# Interface.net
KiCad netlist of a schematic drawn in EAGLE
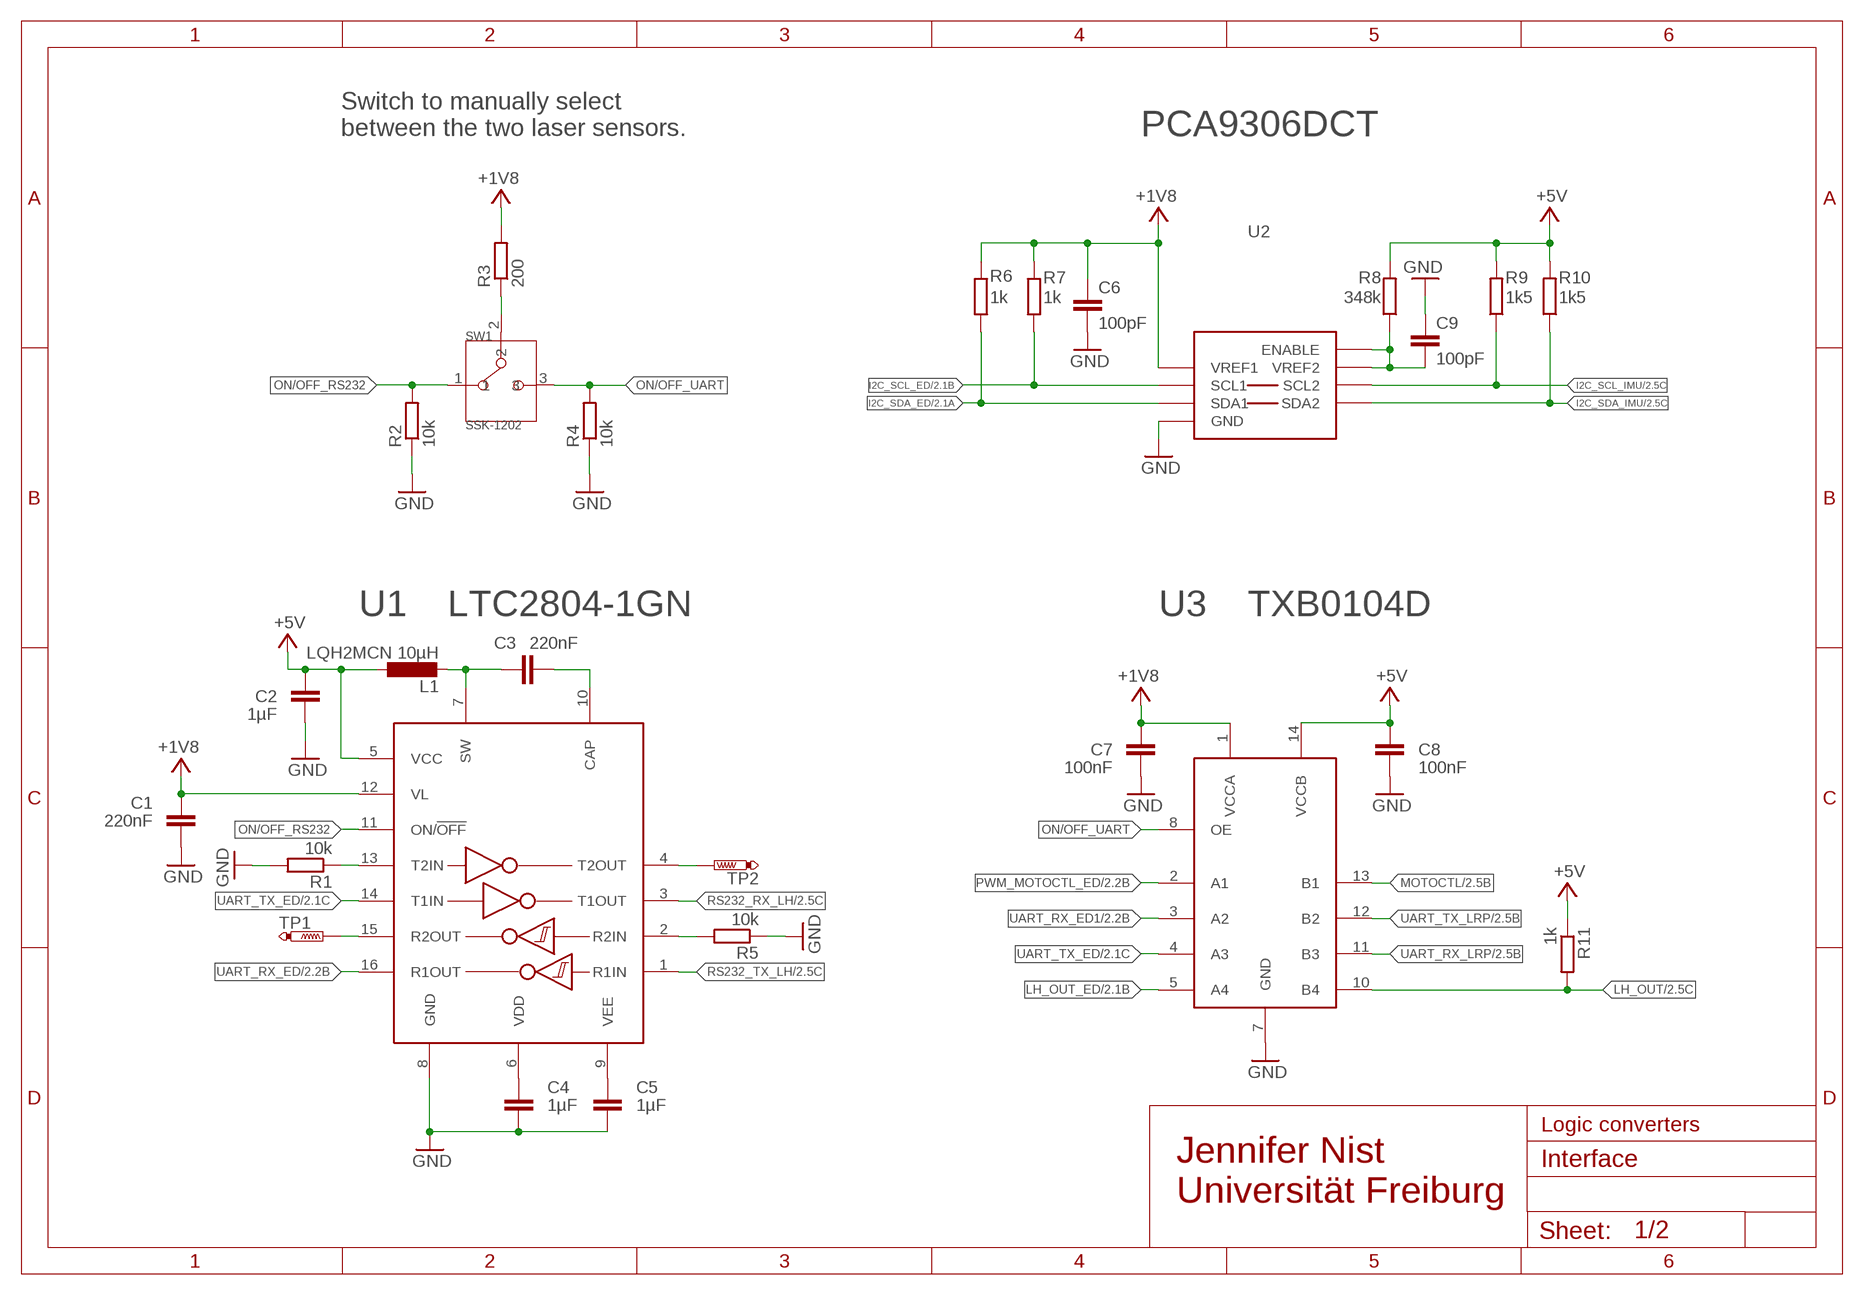
[diagram p0: schematic, sheet 1]
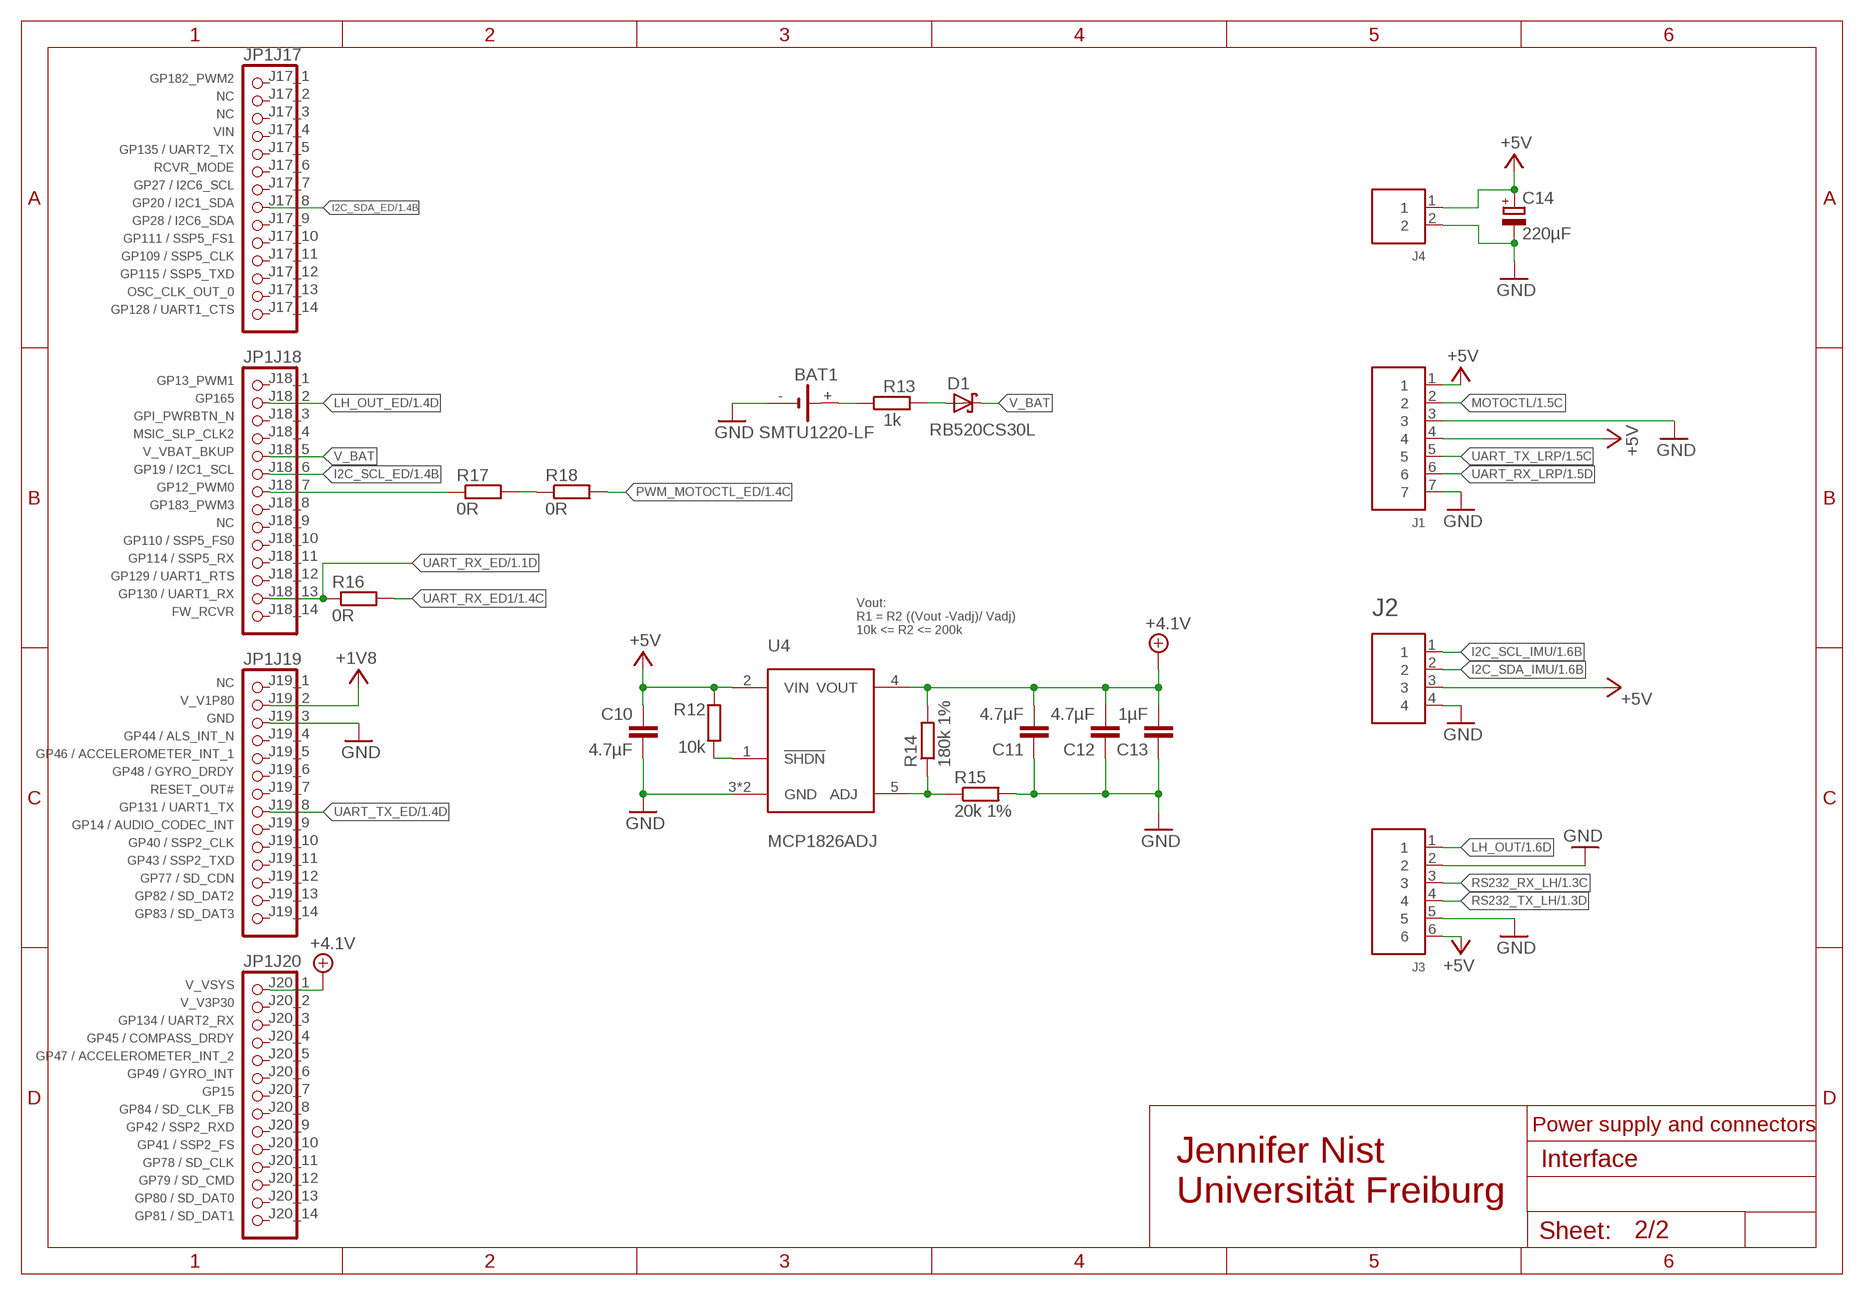
[diagram p1: schematic, sheet 2]

(export (version "E")
  (design (tool "Eeschema 10.0.6"))
  (components
    (comp (ref "BAT1")
      (value "SMTU1220-LF")
      (footprint "eagle-import:SMTU1220-LF")
      (libsource (lib "eagle-import") (part "SMTU1220-LF"))
    )
    (comp (ref "C10")
      (value "4.7µF")
      (footprint "eagle-import:C0805K")
      (libsource (lib "eagle-import") (part "C-EUC0805K"))
    )
    (comp (ref "C11")
      (value "4.7µF")
      (footprint "eagle-import:C0805K")
      (libsource (lib "eagle-import") (part "C-EUC0805K"))
    )
    (comp (ref "C12")
      (value "4.7µF")
      (footprint "eagle-import:C0805K")
      (libsource (lib "eagle-import") (part "C-EUC0805K"))
    )
    (comp (ref "C13")
      (value "1µF")
      (footprint "eagle-import:C0805K")
      (libsource (lib "eagle-import") (part "C-EUC0805K"))
    )
    (comp (ref "C14")
      (value "220µF")
      (footprint "eagle-import:E3,5-8")
      (libsource (lib "eagle-import") (part "CPOL-EUE3.5-8"))
    )
    (comp (ref "D1")
      (value "RB520CS30L")
      (footprint "eagle-import:SOD882")
      (libsource (lib "eagle-import") (part "RB520CS30L"))
    )
    (comp (ref "J1")
      (value "S7B-XH-A90°")
      (footprint "eagle-import:S7B-XH-A")
      (libsource (lib "eagle-import") (part "S7B-XH-A90°"))
    )
    (comp (ref "J2")
      (value "S4B-XH-A90°")
      (footprint "eagle-import:S4B-XH-A")
      (libsource (lib "eagle-import") (part "S4B-XH-A90°"))
    )
    (comp (ref "J3")
      (value "S6B-XH-A90°")
      (footprint "eagle-import:S6B-XH-A")
      (libsource (lib "eagle-import") (part "S6B-XH-A90°"))
    )
    (comp (ref "J4")
      (value "S2B-XH-A90°")
      (footprint "eagle-import:S2B-XH-A")
      (libsource (lib "eagle-import") (part "S2B-XH-A90°"))
    )
    (comp (ref "JP1")
      (value "edison")
      (footprint "eagle-import:1X14")
      (libsource (lib "eagle-import") (part "INTEL_EDISON_BB_HEADER"))
    )
    (comp (ref "R12")
      (value "10k")
      (footprint "eagle-import:R0805")
      (libsource (lib "eagle-import") (part "R-EU_R0805"))
    )
    (comp (ref "R13")
      (value "1k")
      (footprint "eagle-import:R0805")
      (libsource (lib "eagle-import") (part "R-EU_R0805"))
    )
    (comp (ref "R14")
      (value "180k 1%")
      (footprint "eagle-import:R0805")
      (libsource (lib "eagle-import") (part "R-EU_R0805"))
    )
    (comp (ref "R15")
      (value "20k 1%")
      (footprint "eagle-import:R0805")
      (libsource (lib "eagle-import") (part "R-EU_R0805"))
    )
    (comp (ref "R16")
      (value "0R")
      (footprint "eagle-import:R1206")
      (libsource (lib "eagle-import") (part "R-EU_R1206"))
    )
    (comp (ref "R17")
      (value "0R")
      (footprint "eagle-import:R1206")
      (libsource (lib "eagle-import") (part "R-EU_R1206"))
    )
    (comp (ref "R18")
      (value "0R")
      (footprint "eagle-import:R1206")
      (libsource (lib "eagle-import") (part "R-EU_R1206"))
    )
    (comp (ref "U4")
      (value "MCP1826ADJ")
      (footprint "eagle-import:SOT-223-5")
      (libsource (lib "eagle-import") (part "MCP1826ADJ"))
    )
    (comp (ref "C1")
      (value "220nF")
      (footprint "eagle-import:C0805K")
      (libsource (lib "eagle-import") (part "C-EUC0805K"))
    )
    (comp (ref "C2")
      (value "1µF")
      (footprint "eagle-import:C0805K")
      (libsource (lib "eagle-import") (part "C-EUC0805K"))
    )
    (comp (ref "C3")
      (value "220nF")
      (footprint "eagle-import:C0805K")
      (libsource (lib "eagle-import") (part "C-EUC0805K"))
    )
    (comp (ref "C4")
      (value "1µF")
      (footprint "eagle-import:C0805K")
      (libsource (lib "eagle-import") (part "C-EUC0805K"))
    )
    (comp (ref "C5")
      (value "1µF")
      (footprint "eagle-import:C0805K")
      (libsource (lib "eagle-import") (part "C-EUC0805K"))
    )
    (comp (ref "C6")
      (value "100pF")
      (footprint "eagle-import:C0805K")
      (libsource (lib "eagle-import") (part "C-EUC0805K"))
    )
    (comp (ref "C7")
      (value "100nF")
      (footprint "eagle-import:C0805K")
      (libsource (lib "eagle-import") (part "C-EUC0805K"))
    )
    (comp (ref "C8")
      (value "100nF")
      (footprint "eagle-import:C0805K")
      (libsource (lib "eagle-import") (part "C-EUC0805K"))
    )
    (comp (ref "C9")
      (value "100pF")
      (footprint "eagle-import:C0805K")
      (libsource (lib "eagle-import") (part "C-EUC0805K"))
    )
    (comp (ref "L1")
      (value "LQH2MCN 10µH")
      (footprint "eagle-import:L0806")
      (libsource (lib "eagle-import") (part "LQH2MCN"))
    )
    (comp (ref "R1")
      (value "10k")
      (footprint "eagle-import:R0805")
      (libsource (lib "eagle-import") (part "R-EU_R0805"))
    )
    (comp (ref "R2")
      (value "10k")
      (footprint "eagle-import:R0805")
      (libsource (lib "eagle-import") (part "R-EU_R0805"))
    )
    (comp (ref "R3")
      (value "200")
      (footprint "eagle-import:R0805")
      (libsource (lib "eagle-import") (part "R-EU_R0805"))
    )
    (comp (ref "R4")
      (value "10k")
      (footprint "eagle-import:R0805")
      (libsource (lib "eagle-import") (part "R-EU_R0805"))
    )
    (comp (ref "R5")
      (value "10k")
      (footprint "eagle-import:R0805")
      (libsource (lib "eagle-import") (part "R-EU_R0805"))
    )
    (comp (ref "R6")
      (value "1k")
      (footprint "eagle-import:R1206")
      (libsource (lib "eagle-import") (part "R-EU_R1206"))
    )
    (comp (ref "R7")
      (value "1k")
      (footprint "eagle-import:R1206")
      (libsource (lib "eagle-import") (part "R-EU_R1206"))
    )
    (comp (ref "R8")
      (value "348k")
      (footprint "eagle-import:R0805")
      (libsource (lib "eagle-import") (part "R-EU_R0805"))
    )
    (comp (ref "R9")
      (value "1k5")
      (footprint "eagle-import:R1206")
      (libsource (lib "eagle-import") (part "R-EU_R1206"))
    )
    (comp (ref "R10")
      (value "1k5")
      (footprint "eagle-import:R1206")
      (libsource (lib "eagle-import") (part "R-EU_R1206"))
    )
    (comp (ref "R11")
      (value "1k")
      (footprint "eagle-import:R0805")
      (libsource (lib "eagle-import") (part "R-EU_R0805"))
    )
    (comp (ref "SW1")
      (value "SSK-1202")
      (footprint "eagle-import:SSK-1202")
      (libsource (lib "eagle-import") (part "SSK-1202"))
    )
    (comp (ref "TP1")
      (value "PTR1B1,27")
      (footprint "eagle-import:B1,27")
      (libsource (lib "eagle-import") (part "PTR1B1,27"))
    )
    (comp (ref "TP2")
      (value "PTR1B1,27")
      (footprint "eagle-import:B1,27")
      (libsource (lib "eagle-import") (part "PTR1B1,27"))
    )
    (comp (ref "U1")
      (value "LTC2804-1GN")
      (footprint "eagle-import:SSOP-16")
      (libsource (lib "eagle-import") (part "LTC2804-1GN"))
    )
    (comp (ref "U2")
      (value "PCA9306DCT")
      (footprint "eagle-import:SSOP-8")
      (libsource (lib "eagle-import") (part "PCA9306DCT"))
    )
    (comp (ref "U3")
      (value "TXB0104D")
      (footprint "eagle-import:SOIC-14")
      (libsource (lib "eagle-import") (part "TXB0104D"))
    )
  )
  (nets
    (net (code "1") (name "+1V8") (class "Default")
      (node (ref "C1") (pin "2") (pinfunction "2_2") (pintype "passive"))
      (node (ref "C6") (pin "2") (pinfunction "2_2") (pintype "passive"))
      (node (ref "C7") (pin "1") (pinfunction "1_1") (pintype "passive"))
      (node (ref "JP1") (pin "J19_2") (pinfunction "2_J19_2") (pintype "bidirectional"))
      (node (ref "R3") (pin "2") (pinfunction "2_2") (pintype "passive"))
      (node (ref "R6") (pin "1") (pinfunction "1_1") (pintype "passive"))
      (node (ref "R7") (pin "1") (pinfunction "1_1") (pintype "passive"))
      (node (ref "U1") (pin "12") (pinfunction "VL_12") (pintype "bidirectional"))
      (node (ref "U2") (pin "2") (pinfunction "VREF1_2") (pintype "bidirectional"))
      (node (ref "U3") (pin "1") (pinfunction "VCCA_1") (pintype "bidirectional"))
    )
    (net (code "2") (name "+4.1V") (class "Default")
      (node (ref "C11") (pin "2") (pinfunction "2_2") (pintype "passive"))
      (node (ref "C12") (pin "2") (pinfunction "2_2") (pintype "passive"))
      (node (ref "C13") (pin "2") (pinfunction "2_2") (pintype "passive"))
      (node (ref "JP1") (pin "J20_1") (pinfunction "1_J20_1") (pintype "bidirectional"))
      (node (ref "R14") (pin "2") (pinfunction "2_2") (pintype "passive"))
      (node (ref "U4") (pin "4") (pinfunction "VOUT_4") (pintype "bidirectional"))
    )
    (net (code "3") (name "+5V") (class "Default")
      (node (ref "C10") (pin "1") (pinfunction "1_1") (pintype "passive"))
      (node (ref "C14") (pin "+") (pinfunction "+_+") (pintype "passive"))
      (node (ref "C2") (pin "2") (pinfunction "2_2") (pintype "passive"))
      (node (ref "C8") (pin "1") (pinfunction "1_1") (pintype "passive"))
      (node (ref "J1") (pin "1") (pinfunction "1_1") (pintype "passive"))
      (node (ref "J1") (pin "4") (pinfunction "4_4") (pintype "passive"))
      (node (ref "J2") (pin "3") (pinfunction "3_3") (pintype "passive"))
      (node (ref "J3") (pin "6") (pinfunction "6_6") (pintype "passive"))
      (node (ref "J4") (pin "1") (pinfunction "1_1") (pintype "passive"))
      (node (ref "L1") (pin "1") (pinfunction "1_1") (pintype "passive"))
      (node (ref "R10") (pin "2") (pinfunction "2_2") (pintype "passive"))
      (node (ref "R11") (pin "1") (pinfunction "1_1") (pintype "passive"))
      (node (ref "R12") (pin "2") (pinfunction "2_2") (pintype "passive"))
      (node (ref "R8") (pin "2") (pinfunction "2_2") (pintype "passive"))
      (node (ref "R9") (pin "2") (pinfunction "2_2") (pintype "passive"))
      (node (ref "U1") (pin "5") (pinfunction "VCC_5") (pintype "bidirectional"))
      (node (ref "U3") (pin "14") (pinfunction "VCCB_14") (pintype "bidirectional"))
      (node (ref "U4") (pin "2") (pinfunction "VIN_2") (pintype "bidirectional"))
    )
    (net (code "4") (name "GND") (class "Default")
      (node (ref "BAT1") (pin "-") (pinfunction "-_-") (pintype "passive"))
      (node (ref "C1") (pin "1") (pinfunction "1_1") (pintype "passive"))
      (node (ref "C10") (pin "2") (pinfunction "2_2") (pintype "passive"))
      (node (ref "C11") (pin "1") (pinfunction "1_1") (pintype "passive"))
      (node (ref "C12") (pin "1") (pinfunction "1_1") (pintype "passive"))
      (node (ref "C13") (pin "1") (pinfunction "1_1") (pintype "passive"))
      (node (ref "C14") (pin "-") (pinfunction "-_-") (pintype "passive"))
      (node (ref "C2") (pin "1") (pinfunction "1_1") (pintype "passive"))
      (node (ref "C4") (pin "2") (pinfunction "2_2") (pintype "passive"))
      (node (ref "C5") (pin "2") (pinfunction "2_2") (pintype "passive"))
      (node (ref "C6") (pin "1") (pinfunction "1_1") (pintype "passive"))
      (node (ref "C7") (pin "2") (pinfunction "2_2") (pintype "passive"))
      (node (ref "C8") (pin "2") (pinfunction "2_2") (pintype "passive"))
      (node (ref "C9") (pin "2") (pinfunction "2_2") (pintype "passive"))
      (node (ref "J1") (pin "3") (pinfunction "3_3") (pintype "passive"))
      (node (ref "J1") (pin "7") (pinfunction "7_7") (pintype "passive"))
      (node (ref "J2") (pin "4") (pinfunction "4_4") (pintype "passive"))
      (node (ref "J3") (pin "2") (pinfunction "2_2") (pintype "passive"))
      (node (ref "J3") (pin "5") (pinfunction "5_5") (pintype "passive"))
      (node (ref "J4") (pin "2") (pinfunction "2_2") (pintype "passive"))
      (node (ref "JP1") (pin "J19_3") (pinfunction "3_J19_3") (pintype "bidirectional"))
      (node (ref "R1") (pin "2") (pinfunction "2_2") (pintype "passive"))
      (node (ref "R15") (pin "2") (pinfunction "2_2") (pintype "passive"))
      (node (ref "R2") (pin "1") (pinfunction "1_1") (pintype "passive"))
      (node (ref "R4") (pin "1") (pinfunction "1_1") (pintype "passive"))
      (node (ref "R5") (pin "1") (pinfunction "1_1") (pintype "passive"))
      (node (ref "U1") (pin "8") (pinfunction "GND_8") (pintype "bidirectional"))
      (node (ref "U2") (pin "1") (pinfunction "GND_1") (pintype "power_in"))
      (node (ref "U3") (pin "7") (pinfunction "GND_7") (pintype "power_in"))
      (node (ref "U4") (pin "3") (pinfunction "GND_3") (pintype "power_in"))
      (node (ref "U4") (pin "TAB") (pinfunction "GND_TAB") (pintype "power_in"))
    )
    (net (code "5") (name "I2C_SCL_ED") (class "Default")
      (node (ref "JP1") (pin "J18_6") (pinfunction "6_J18_6") (pintype "bidirectional"))
      (node (ref "R7") (pin "2") (pinfunction "2_2") (pintype "passive"))
      (node (ref "U2") (pin "3") (pinfunction "SCL1_3") (pintype "bidirectional"))
    )
    (net (code "6") (name "I2C_SCL_IMU") (class "Default")
      (node (ref "J2") (pin "1") (pinfunction "1_1") (pintype "passive"))
      (node (ref "R9") (pin "1") (pinfunction "1_1") (pintype "passive"))
      (node (ref "U2") (pin "6") (pinfunction "SCL2_6") (pintype "bidirectional"))
    )
    (net (code "7") (name "I2C_SDA_ED") (class "Default")
      (node (ref "JP1") (pin "J17_8") (pinfunction "8_J17_8") (pintype "bidirectional"))
      (node (ref "R6") (pin "2") (pinfunction "2_2") (pintype "passive"))
      (node (ref "U2") (pin "4") (pinfunction "SDA1_4") (pintype "bidirectional"))
    )
    (net (code "8") (name "I2C_SDA_IMU") (class "Default")
      (node (ref "J2") (pin "2") (pinfunction "2_2") (pintype "passive"))
      (node (ref "R10") (pin "1") (pinfunction "1_1") (pintype "passive"))
      (node (ref "U2") (pin "5") (pinfunction "SDA2_5") (pintype "bidirectional"))
    )
    (net (code "9") (name "LH_OUT") (class "Default")
      (node (ref "J3") (pin "1") (pinfunction "1_1") (pintype "passive"))
      (node (ref "R11") (pin "2") (pinfunction "2_2") (pintype "passive"))
      (node (ref "U3") (pin "10") (pinfunction "B4_10") (pintype "bidirectional"))
    )
    (net (code "10") (name "LH_OUT_ED") (class "Default")
      (node (ref "JP1") (pin "J18_2") (pinfunction "2_J18_2") (pintype "bidirectional"))
      (node (ref "U3") (pin "5") (pinfunction "A4_5") (pintype "bidirectional"))
    )
    (net (code "11") (name "MOTOCTL") (class "Default")
      (node (ref "J1") (pin "2") (pinfunction "2_2") (pintype "passive"))
      (node (ref "U3") (pin "13") (pinfunction "B1_13") (pintype "bidirectional"))
    )
    (net (code "12") (name "Net-(BAT1-Pad+)") (class "Default")
      (node (ref "BAT1") (pin "+") (pinfunction "+_+") (pintype "passive"))
      (node (ref "R13") (pin "1") (pinfunction "1_1") (pintype "passive"))
    )
    (net (code "13") (name "Net-(D1-PadA)") (class "Default")
      (node (ref "D1") (pin "A") (pinfunction "A_A") (pintype "passive"))
      (node (ref "R13") (pin "2") (pinfunction "2_2") (pintype "passive"))
    )
    (net (code "14") (name "Net-(JP1B-7)") (class "Default")
      (node (ref "JP1") (pin "J18_7") (pinfunction "7_J18_7") (pintype "bidirectional"))
      (node (ref "R17") (pin "1") (pinfunction "1_1") (pintype "passive"))
    )
    (net (code "15") (name "Net-(R3-Pad1)") (class "Default")
      (node (ref "R3") (pin "1") (pinfunction "1_1") (pintype "passive"))
      (node (ref "SW1") (pin "2") (pinfunction "2_2") (pintype "bidirectional"))
    )
    (net (code "16") (name "Net-(R17-Pad2)") (class "Default")
      (node (ref "R17") (pin "2") (pinfunction "2_2") (pintype "passive"))
      (node (ref "R18") (pin "1") (pinfunction "1_1") (pintype "passive"))
    )
    (net (code "17") (name "Net-(U1-CAP)") (class "Default")
      (node (ref "C3") (pin "2") (pinfunction "2_2") (pintype "passive"))
      (node (ref "U1") (pin "10") (pinfunction "CAP_10") (pintype "bidirectional"))
    )
    (net (code "18") (name "Net-(U1-R2IN)") (class "Default")
      (node (ref "R5") (pin "2") (pinfunction "2_2") (pintype "passive"))
      (node (ref "U1") (pin "2") (pinfunction "R2IN_2") (pintype "bidirectional"))
    )
    (net (code "19") (name "Net-(U1-R2OUT)") (class "Default")
      (node (ref "TP1") (pin "TP") (pinfunction "TP_TP") (pintype "input"))
      (node (ref "U1") (pin "15") (pinfunction "R2OUT_15") (pintype "bidirectional"))
    )
    (net (code "20") (name "Net-(U1-SW)") (class "Default")
      (node (ref "C3") (pin "1") (pinfunction "1_1") (pintype "passive"))
      (node (ref "L1") (pin "2") (pinfunction "2_2") (pintype "passive"))
      (node (ref "U1") (pin "7") (pinfunction "SW_7") (pintype "bidirectional"))
    )
    (net (code "21") (name "Net-(U1-T2IN)") (class "Default")
      (node (ref "R1") (pin "1") (pinfunction "1_1") (pintype "passive"))
      (node (ref "U1") (pin "13") (pinfunction "T2IN_13") (pintype "bidirectional"))
    )
    (net (code "22") (name "Net-(U1-T2OUT)") (class "Default")
      (node (ref "TP2") (pin "TP") (pinfunction "TP_TP") (pintype "input"))
      (node (ref "U1") (pin "4") (pinfunction "T2OUT_4") (pintype "bidirectional"))
    )
    (net (code "23") (name "Net-(U1-VDD)") (class "Default")
      (node (ref "C4") (pin "1") (pinfunction "1_1") (pintype "passive"))
      (node (ref "U1") (pin "6") (pinfunction "VDD_6") (pintype "power_in"))
    )
    (net (code "24") (name "Net-(U1-VEE)") (class "Default")
      (node (ref "C5") (pin "1") (pinfunction "1_1") (pintype "passive"))
      (node (ref "U1") (pin "9") (pinfunction "VEE_9") (pintype "power_in"))
    )
    (net (code "25") (name "Net-(U2-ENABLE)") (class "Default")
      (node (ref "C9") (pin "1") (pinfunction "1_1") (pintype "passive"))
      (node (ref "R8") (pin "1") (pinfunction "1_1") (pintype "passive"))
      (node (ref "U2") (pin "7") (pinfunction "VREF2_7") (pintype "bidirectional"))
      (node (ref "U2") (pin "8") (pinfunction "ENABLE_8") (pintype "input"))
    )
    (net (code "26") (name "Net-(U4-ADJ)") (class "Default")
      (node (ref "R14") (pin "1") (pinfunction "1_1") (pintype "passive"))
      (node (ref "R15") (pin "1") (pinfunction "1_1") (pintype "passive"))
      (node (ref "U4") (pin "5") (pinfunction "ADJ_5") (pintype "input"))
    )
    (net (code "27") (name "Net-(U4-~{SHDN})") (class "Default")
      (node (ref "R12") (pin "1") (pinfunction "1_1") (pintype "passive"))
      (node (ref "U4") (pin "1") (pinfunction "~{SHDN}_1") (pintype "input"))
    )
    (net (code "28") (name "ON{slash}OFF_RS232") (class "Default")
      (node (ref "R2") (pin "2") (pinfunction "2_2") (pintype "passive"))
      (node (ref "SW1") (pin "1") (pinfunction "1_1") (pintype "bidirectional"))
      (node (ref "U1") (pin "11") (pinfunction "ON/~{OFF}_11") (pintype "bidirectional"))
    )
    (net (code "29") (name "ON{slash}OFF_UART") (class "Default")
      (node (ref "R4") (pin "2") (pinfunction "2_2") (pintype "passive"))
      (node (ref "SW1") (pin "3") (pinfunction "3_3") (pintype "bidirectional"))
      (node (ref "U3") (pin "8") (pinfunction "OE_8") (pintype "bidirectional"))
    )
    (net (code "30") (name "PWM_MOTOCTL_ED") (class "Default")
      (node (ref "R18") (pin "2") (pinfunction "2_2") (pintype "passive"))
      (node (ref "U3") (pin "2") (pinfunction "A1_2") (pintype "bidirectional"))
    )
    (net (code "31") (name "RS232_RX_LH") (class "Default")
      (node (ref "J3") (pin "3") (pinfunction "3_3") (pintype "passive"))
      (node (ref "U1") (pin "3") (pinfunction "T1OUT_3") (pintype "bidirectional"))
    )
    (net (code "32") (name "RS232_TX_LH") (class "Default")
      (node (ref "J3") (pin "4") (pinfunction "4_4") (pintype "passive"))
      (node (ref "U1") (pin "1") (pinfunction "R1IN_1") (pintype "bidirectional"))
    )
    (net (code "33") (name "UART_RX_ED") (class "Default")
      (node (ref "JP1") (pin "J18_13") (pinfunction "13_J18_13") (pintype "bidirectional"))
      (node (ref "R16") (pin "1") (pinfunction "1_1") (pintype "passive"))
      (node (ref "U1") (pin "16") (pinfunction "R1OUT_16") (pintype "bidirectional"))
    )
    (net (code "34") (name "UART_RX_ED1") (class "Default")
      (node (ref "R16") (pin "2") (pinfunction "2_2") (pintype "passive"))
      (node (ref "U3") (pin "3") (pinfunction "A2_3") (pintype "bidirectional"))
    )
    (net (code "35") (name "UART_RX_LRP") (class "Default")
      (node (ref "J1") (pin "6") (pinfunction "6_6") (pintype "passive"))
      (node (ref "U3") (pin "11") (pinfunction "B3_11") (pintype "bidirectional"))
    )
    (net (code "36") (name "UART_TX_ED") (class "Default")
      (node (ref "JP1") (pin "J19_8") (pinfunction "8_J19_8") (pintype "bidirectional"))
      (node (ref "U1") (pin "14") (pinfunction "T1IN_14") (pintype "bidirectional"))
      (node (ref "U3") (pin "4") (pinfunction "A3_4") (pintype "bidirectional"))
    )
    (net (code "37") (name "UART_TX_LRP") (class "Default")
      (node (ref "J1") (pin "5") (pinfunction "5_5") (pintype "passive"))
      (node (ref "U3") (pin "12") (pinfunction "B2_12") (pintype "bidirectional"))
    )
    (net (code "38") (name "V_BAT") (class "Default")
      (node (ref "D1") (pin "C") (pinfunction "C_C") (pintype "passive"))
      (node (ref "JP1") (pin "J18_5") (pinfunction "5_J18_5") (pintype "bidirectional"))
    )
    (net (code "39") (name "unconnected-(JP1A-1-PadJ17_1)") (class "Default")
      (node (ref "JP1") (pin "J17_1") (pinfunction "1_J17_1") (pintype "bidirectional"))
    )
    (net (code "40") (name "unconnected-(JP1A-2-PadJ17_2)") (class "Default")
      (node (ref "JP1") (pin "J17_2") (pinfunction "2_J17_2") (pintype "no_connect"))
    )
    (net (code "41") (name "unconnected-(JP1A-3-PadJ17_3)") (class "Default")
      (node (ref "JP1") (pin "J17_3") (pinfunction "3_J17_3") (pintype "no_connect"))
    )
    (net (code "42") (name "unconnected-(JP1A-4-PadJ17_4)") (class "Default")
      (node (ref "JP1") (pin "J17_4") (pinfunction "4_J17_4") (pintype "bidirectional"))
    )
    (net (code "43") (name "unconnected-(JP1A-5-PadJ17_5)") (class "Default")
      (node (ref "JP1") (pin "J17_5") (pinfunction "5_J17_5") (pintype "bidirectional"))
    )
    (net (code "44") (name "unconnected-(JP1A-6-PadJ17_6)") (class "Default")
      (node (ref "JP1") (pin "J17_6") (pinfunction "6_J17_6") (pintype "bidirectional"))
    )
    (net (code "45") (name "unconnected-(JP1A-7-PadJ17_7)") (class "Default")
      (node (ref "JP1") (pin "J17_7") (pinfunction "7_J17_7") (pintype "bidirectional"))
    )
    (net (code "46") (name "unconnected-(JP1A-9-PadJ17_9)") (class "Default")
      (node (ref "JP1") (pin "J17_9") (pinfunction "9_J17_9") (pintype "bidirectional"))
    )
    (net (code "47") (name "unconnected-(JP1A-10-PadJ17_10)") (class "Default")
      (node (ref "JP1") (pin "J17_10") (pinfunction "10_J17_10") (pintype "bidirectional"))
    )
    (net (code "48") (name "unconnected-(JP1A-11-PadJ17_11)") (class "Default")
      (node (ref "JP1") (pin "J17_11") (pinfunction "11_J17_11") (pintype "bidirectional"))
    )
    (net (code "49") (name "unconnected-(JP1A-12-PadJ17_12)") (class "Default")
      (node (ref "JP1") (pin "J17_12") (pinfunction "12_J17_12") (pintype "bidirectional"))
    )
    (net (code "50") (name "unconnected-(JP1A-13-PadJ17_13)") (class "Default")
      (node (ref "JP1") (pin "J17_13") (pinfunction "13_J17_13") (pintype "bidirectional"))
    )
    (net (code "51") (name "unconnected-(JP1A-14-PadJ17_14)") (class "Default")
      (node (ref "JP1") (pin "J17_14") (pinfunction "14_J17_14") (pintype "bidirectional"))
    )
    (net (code "52") (name "unconnected-(JP1B-1-PadJ18_1)") (class "Default")
      (node (ref "JP1") (pin "J18_1") (pinfunction "1_J18_1") (pintype "bidirectional"))
    )
    (net (code "53") (name "unconnected-(JP1B-3-PadJ18_3)") (class "Default")
      (node (ref "JP1") (pin "J18_3") (pinfunction "3_J18_3") (pintype "bidirectional"))
    )
    (net (code "54") (name "unconnected-(JP1B-4-PadJ18_4)") (class "Default")
      (node (ref "JP1") (pin "J18_4") (pinfunction "4_J18_4") (pintype "bidirectional"))
    )
    (net (code "55") (name "unconnected-(JP1B-8-PadJ18_8)") (class "Default")
      (node (ref "JP1") (pin "J18_8") (pinfunction "8_J18_8") (pintype "bidirectional"))
    )
    (net (code "56") (name "unconnected-(JP1B-9-PadJ18_9)") (class "Default")
      (node (ref "JP1") (pin "J18_9") (pinfunction "9_J18_9") (pintype "no_connect"))
    )
    (net (code "57") (name "unconnected-(JP1B-10-PadJ18_10)") (class "Default")
      (node (ref "JP1") (pin "J18_10") (pinfunction "10_J18_10") (pintype "bidirectional"))
    )
    (net (code "58") (name "unconnected-(JP1B-11-PadJ18_11)") (class "Default")
      (node (ref "JP1") (pin "J18_11") (pinfunction "11_J18_11") (pintype "bidirectional"))
    )
    (net (code "59") (name "unconnected-(JP1B-12-PadJ18_12)") (class "Default")
      (node (ref "JP1") (pin "J18_12") (pinfunction "12_J18_12") (pintype "bidirectional"))
    )
    (net (code "60") (name "unconnected-(JP1B-14-PadJ18_14)") (class "Default")
      (node (ref "JP1") (pin "J18_14") (pinfunction "14_J18_14") (pintype "bidirectional"))
    )
    (net (code "61") (name "unconnected-(JP1C-1-PadJ19_1)") (class "Default")
      (node (ref "JP1") (pin "J19_1") (pinfunction "1_J19_1") (pintype "no_connect"))
    )
    (net (code "62") (name "unconnected-(JP1C-4-PadJ19_4)") (class "Default")
      (node (ref "JP1") (pin "J19_4") (pinfunction "4_J19_4") (pintype "bidirectional"))
    )
    (net (code "63") (name "unconnected-(JP1C-5-PadJ19_5)") (class "Default")
      (node (ref "JP1") (pin "J19_5") (pinfunction "5_J19_5") (pintype "bidirectional"))
    )
    (net (code "64") (name "unconnected-(JP1C-6-PadJ19_6)") (class "Default")
      (node (ref "JP1") (pin "J19_6") (pinfunction "6_J19_6") (pintype "bidirectional"))
    )
    (net (code "65") (name "unconnected-(JP1C-7-PadJ19_7)") (class "Default")
      (node (ref "JP1") (pin "J19_7") (pinfunction "7_J19_7") (pintype "bidirectional"))
    )
    (net (code "66") (name "unconnected-(JP1C-9-PadJ19_9)") (class "Default")
      (node (ref "JP1") (pin "J19_9") (pinfunction "9_J19_9") (pintype "bidirectional"))
    )
    (net (code "67") (name "unconnected-(JP1C-10-PadJ19_10)") (class "Default")
      (node (ref "JP1") (pin "J19_10") (pinfunction "10_J19_10") (pintype "bidirectional"))
    )
    (net (code "68") (name "unconnected-(JP1C-11-PadJ19_11)") (class "Default")
      (node (ref "JP1") (pin "J19_11") (pinfunction "11_J19_11") (pintype "bidirectional"))
    )
    (net (code "69") (name "unconnected-(JP1C-12-PadJ19_12)") (class "Default")
      (node (ref "JP1") (pin "J19_12") (pinfunction "12_J19_12") (pintype "bidirectional"))
    )
    (net (code "70") (name "unconnected-(JP1C-13-PadJ19_13)") (class "Default")
      (node (ref "JP1") (pin "J19_13") (pinfunction "13_J19_13") (pintype "bidirectional"))
    )
    (net (code "71") (name "unconnected-(JP1C-14-PadJ19_14)") (class "Default")
      (node (ref "JP1") (pin "J19_14") (pinfunction "14_J19_14") (pintype "bidirectional"))
    )
    (net (code "72") (name "unconnected-(JP1D-2-PadJ20_2)") (class "Default")
      (node (ref "JP1") (pin "J20_2") (pinfunction "2_J20_2") (pintype "bidirectional"))
    )
    (net (code "73") (name "unconnected-(JP1D-3-PadJ20_3)") (class "Default")
      (node (ref "JP1") (pin "J20_3") (pinfunction "3_J20_3") (pintype "bidirectional"))
    )
    (net (code "74") (name "unconnected-(JP1D-4-PadJ20_4)") (class "Default")
      (node (ref "JP1") (pin "J20_4") (pinfunction "4_J20_4") (pintype "bidirectional"))
    )
    (net (code "75") (name "unconnected-(JP1D-5-PadJ20_5)") (class "Default")
      (node (ref "JP1") (pin "J20_5") (pinfunction "5_J20_5") (pintype "bidirectional"))
    )
    (net (code "76") (name "unconnected-(JP1D-6-PadJ20_6)") (class "Default")
      (node (ref "JP1") (pin "J20_6") (pinfunction "6_J20_6") (pintype "bidirectional"))
    )
    (net (code "77") (name "unconnected-(JP1D-7-PadJ20_7)") (class "Default")
      (node (ref "JP1") (pin "J20_7") (pinfunction "7_J20_7") (pintype "bidirectional"))
    )
    (net (code "78") (name "unconnected-(JP1D-8-PadJ20_8)") (class "Default")
      (node (ref "JP1") (pin "J20_8") (pinfunction "8_J20_8") (pintype "bidirectional"))
    )
    (net (code "79") (name "unconnected-(JP1D-9-PadJ20_9)") (class "Default")
      (node (ref "JP1") (pin "J20_9") (pinfunction "9_J20_9") (pintype "bidirectional"))
    )
    (net (code "80") (name "unconnected-(JP1D-10-PadJ20_10)") (class "Default")
      (node (ref "JP1") (pin "J20_10") (pinfunction "10_J20_10") (pintype "bidirectional"))
    )
    (net (code "81") (name "unconnected-(JP1D-11-PadJ20_11)") (class "Default")
      (node (ref "JP1") (pin "J20_11") (pinfunction "11_J20_11") (pintype "bidirectional"))
    )
    (net (code "82") (name "unconnected-(JP1D-12-PadJ20_12)") (class "Default")
      (node (ref "JP1") (pin "J20_12") (pinfunction "12_J20_12") (pintype "bidirectional"))
    )
    (net (code "83") (name "unconnected-(JP1D-13-PadJ20_13)") (class "Default")
      (node (ref "JP1") (pin "J20_13") (pinfunction "13_J20_13") (pintype "bidirectional"))
    )
    (net (code "84") (name "unconnected-(JP1D-14-PadJ20_14)") (class "Default")
      (node (ref "JP1") (pin "J20_14") (pinfunction "14_J20_14") (pintype "bidirectional"))
    )
  )
)
